# FPGA_Config_GPMC.net
KiCad netlist of a schematic drawn in Altium Designer
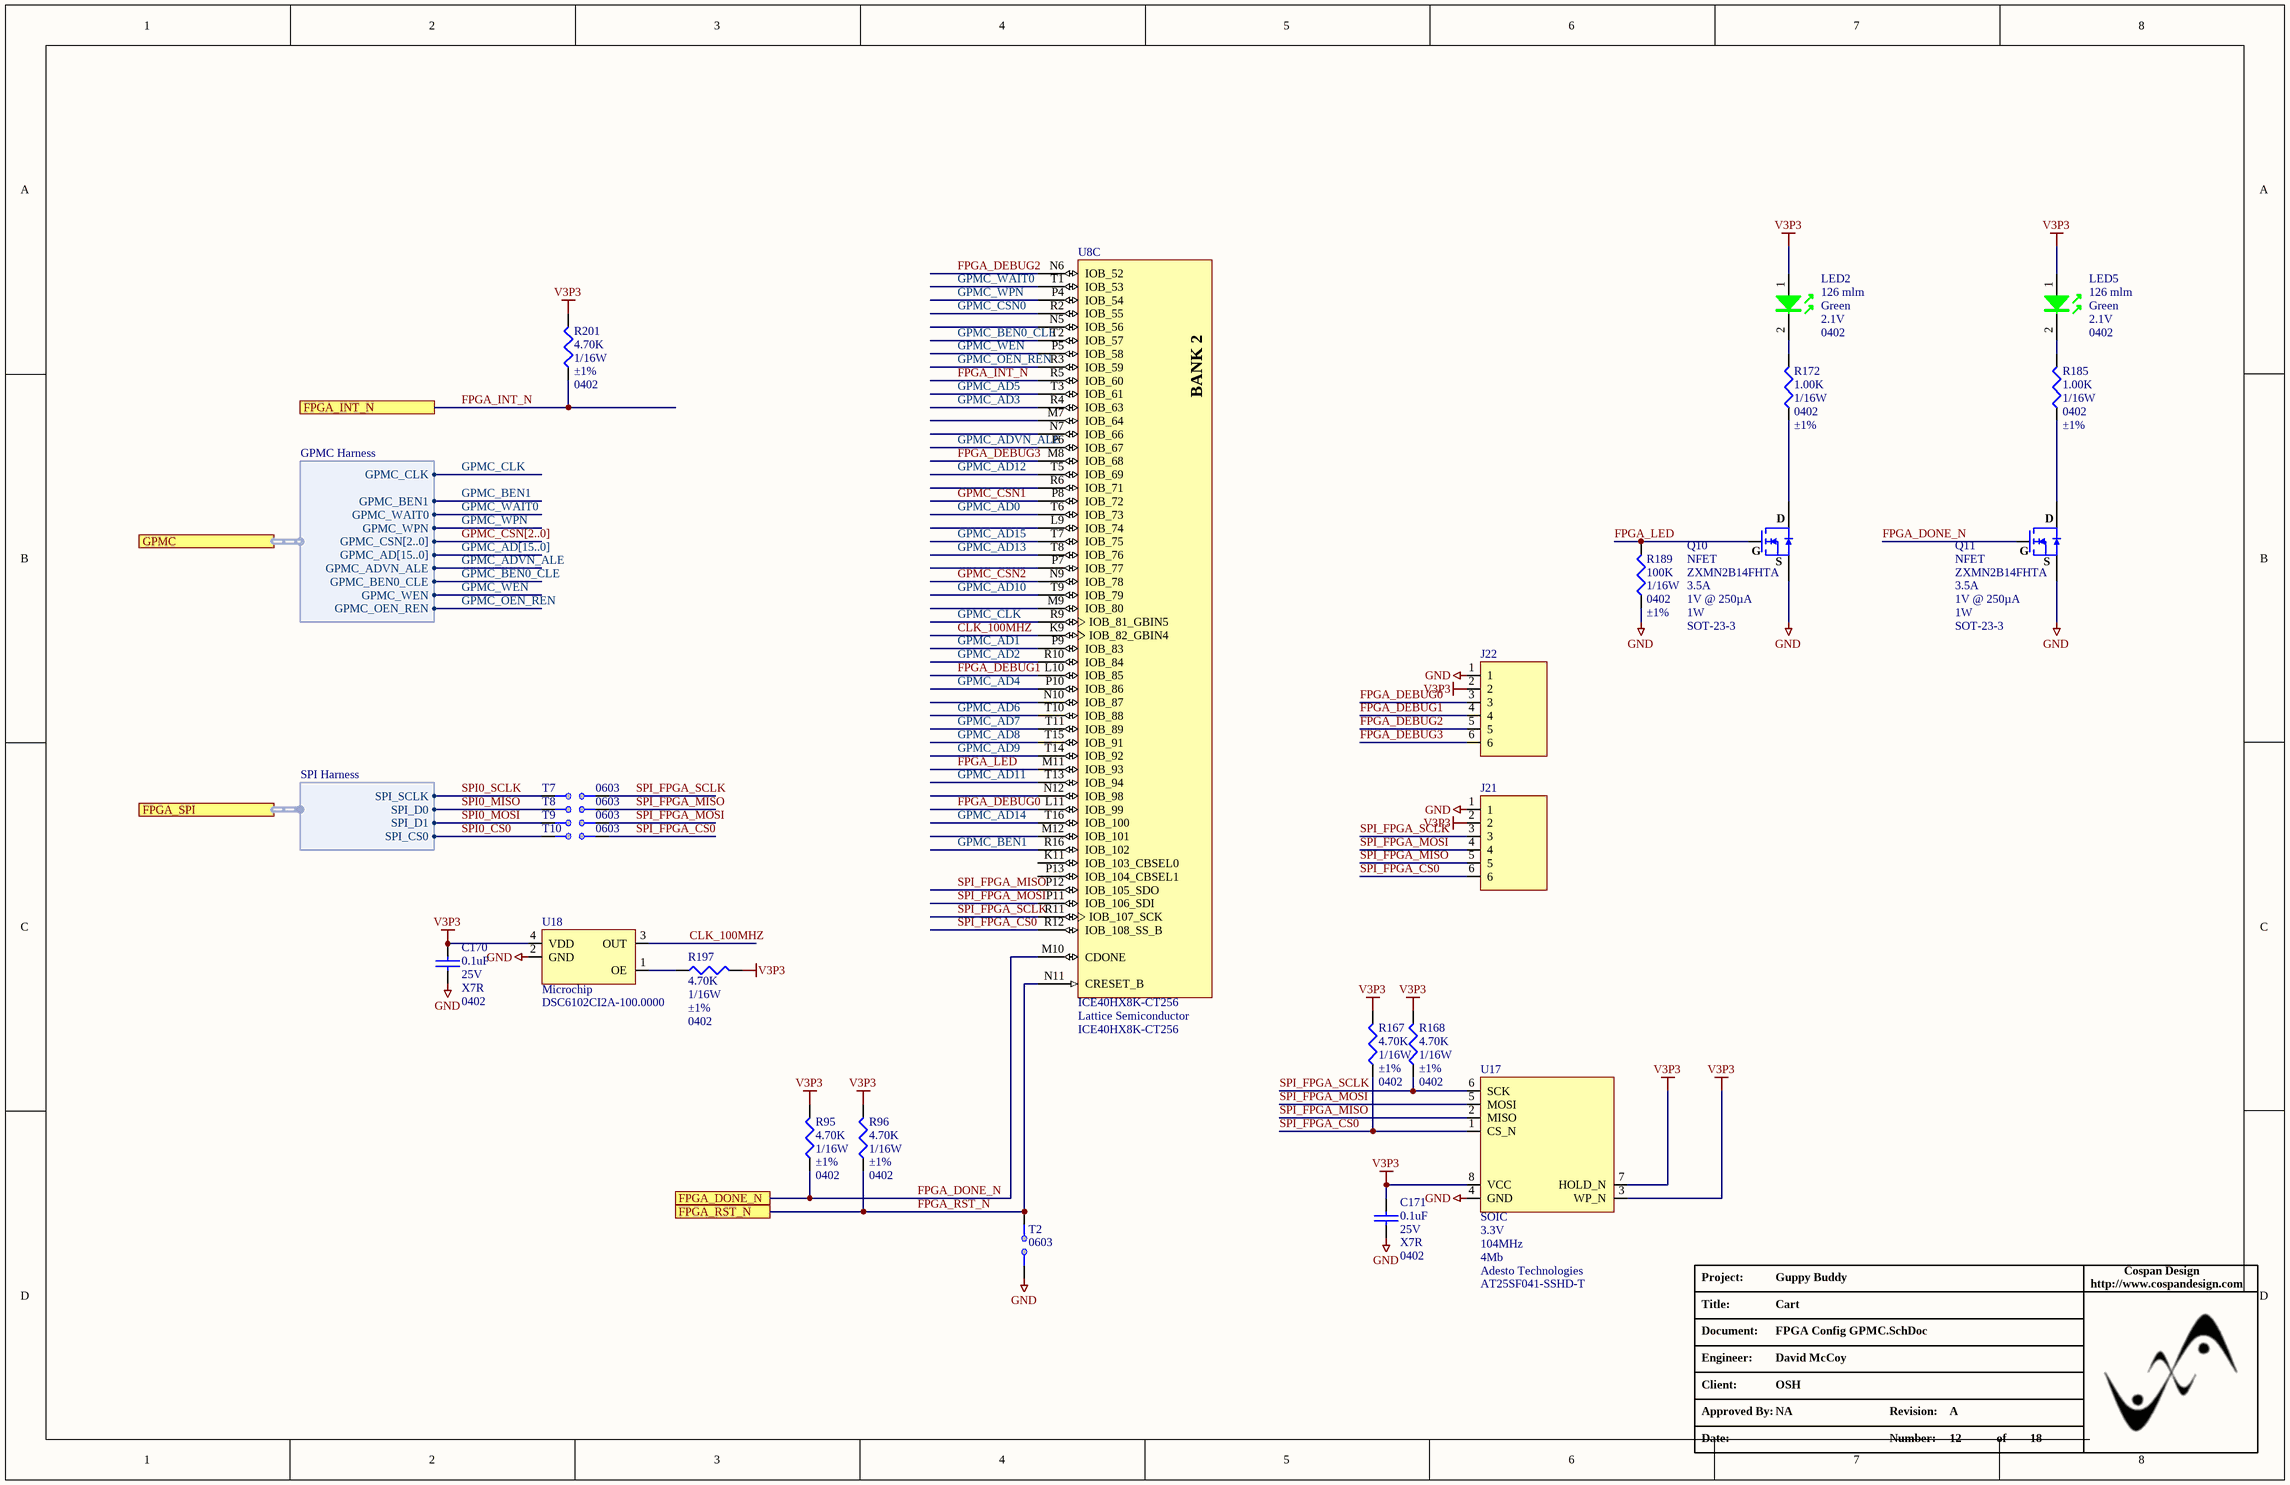
[diagram p0: FPGA Config GPMC.SchDoc]

(export (version "E")
  (design (tool "Eeschema 10.0.6"))
  (components
    (comp (ref "C170")
      (value "C_0402_0.1UF_25V")
      (footprint "C_0402")
      (description "CAP CER 0.1UF 25V X6S 0402")
      (fields
        (field (name "TOLERANCE") "10%")
        (field (name "CAPACITANCE") "0.1uF")
        (field (name "VOLTAGE - RATED") "25V")
        (field (name "TEMPERATURE COEFFICIENT") "X7R")
        (field (name "PACKAGE / CASE") "0402")
      )
      (libsource (lib "Cospan Design") (part "C_0402_0.1UF_25V"))
    )
    (comp (ref "C171")
      (value "C_0402_0.1UF_25V")
      (footprint "C_0402")
      (description "CAP CER 0.1UF 25V X6S 0402")
      (fields
        (field (name "TOLERANCE") "10%")
        (field (name "CAPACITANCE") "0.1uF")
        (field (name "VOLTAGE - RATED") "25V")
        (field (name "TEMPERATURE COEFFICIENT") "X7R")
        (field (name "PACKAGE / CASE") "0402")
      )
      (libsource (lib "Cospan Design") (part "C_0402_0.1UF_25V"))
    )
    (comp (ref "J21")
      (value "J_HDR_1X6_HOLES")
      (footprint "HDR_1X6 _HOLES")
      (description "6 Holes")
      (libsource (lib "Cospan Design") (part "J_HDR_1X6_HOLES"))
    )
    (comp (ref "J22")
      (value "J_HDR_1X6_HOLES")
      (footprint "HDR_1X6 _HOLES")
      (description "6 Holes")
      (libsource (lib "Cospan Design") (part "J_HDR_1X6_HOLES"))
    )
    (comp (ref "LED2")
      (value "LED_GRN_0402")
      (footprint "DIOM1005X07L_GREEN")
      (description "LED 1X0.5MM 570NM GN WTR CLR SMD")
      (fields
        (field (name "MANUFACTURER") "Kingbright Corp")
        (field (name "MANUFACTURER PART NUMBER") "APHHS1005CGCK")
        (field (name "LUMINOUS FLUX @ CURRENT - TEST") "126 mlm")
        (field (name "COLOR") "Green")
        (field (name "VOLTAGE - FORWARD (VF) TYP") "2.1V")
        (field (name "PACKAGE / CASE") "0402")
      )
      (libsource (lib "Main Library") (part "LED_GRN_0402"))
    )
    (comp (ref "LED5")
      (value "LED_GRN_0402")
      (footprint "DIOM1005X07L_GREEN")
      (description "LED 1X0.5MM 570NM GN WTR CLR SMD")
      (fields
        (field (name "MANUFACTURER") "Kingbright Corp")
        (field (name "MANUFACTURER PART NUMBER") "APHHS1005CGCK")
        (field (name "LUMINOUS FLUX @ CURRENT - TEST") "126 mlm")
        (field (name "COLOR") "Green")
        (field (name "VOLTAGE - FORWARD (VF) TYP") "2.1V")
        (field (name "PACKAGE / CASE") "0402")
      )
      (libsource (lib "Main Library") (part "LED_GRN_0402"))
    )
    (comp (ref "Q10")
      (value "NFET")
      (footprint "SOT-23A")
      (description "MOSFET N-CH 20V 3.5A SOT23-3")
      (fields
        (field (name "MANUFACTURER") "Diodes Incorporated")
        (field (name "MANUFACTURER PART NUMBER") "ZXMN2B14FHTA")
        (field (name "CURRENT - CONTINUOUS DRAIN (ID) @ 25° C") "3.5A")
        (field (name "VGS(TH) (MAX) @ ID") "1V @ 250µA")
        (field (name "POWER - MAX") "1W")
        (field (name "PACKAGE / CASE") "SOT-23-3")
      )
      (libsource (lib "Main LibraryX") (part "Q_NFET_3.50A_SOT23"))
    )
    (comp (ref "Q11")
      (value "NFET")
      (footprint "SOT-23A")
      (description "MOSFET N-CH 20V 3.5A SOT23-3")
      (fields
        (field (name "MANUFACTURER") "Diodes Incorporated")
        (field (name "MANUFACTURER PART NUMBER") "ZXMN2B14FHTA")
        (field (name "CURRENT - CONTINUOUS DRAIN (ID) @ 25° C") "3.5A")
        (field (name "VGS(TH) (MAX) @ ID") "1V @ 250µA")
        (field (name "POWER - MAX") "1W")
        (field (name "PACKAGE / CASE") "SOT-23-3")
      )
      (libsource (lib "Main LibraryX") (part "Q_NFET_3.50A_SOT23"))
    )
    (comp (ref "R95")
      (value "4.7k Ohms")
      (footprint "R_0402")
      (description "RES 4.70K OHM 1/16W 1% 0402 SMD")
      (fields
        (field (name "MANUFACTURER") "Yageo")
        (field (name "MANUFACTURER PART NUMBER") "RC0402FR-074K7L")
        (field (name "RESISTANCE IN OHMS") "4.70K")
        (field (name "POWER (WATTS)") "1/16W")
        (field (name "TOLERANCE") "±1%")
        (field (name "CASE") "0402")
      )
      (libsource (lib "Main Library") (part "R_0402_4.70K"))
    )
    (comp (ref "R96")
      (value "4.7k Ohms")
      (footprint "R_0402")
      (description "RES 4.70K OHM 1/16W 1% 0402 SMD")
      (fields
        (field (name "MANUFACTURER") "Yageo")
        (field (name "MANUFACTURER PART NUMBER") "RC0402FR-074K7L")
        (field (name "RESISTANCE IN OHMS") "4.70K")
        (field (name "POWER (WATTS)") "1/16W")
        (field (name "TOLERANCE") "±1%")
        (field (name "CASE") "0402")
      )
      (libsource (lib "Main Library") (part "R_0402_4.70K"))
    )
    (comp (ref "R167")
      (value "4.7k Ohms")
      (footprint "R_0402")
      (description "RES 4.70K OHM 1/16W 1% 0402 SMD")
      (fields
        (field (name "MANUFACTURER") "Yageo")
        (field (name "MANUFACTURER PART NUMBER") "RC0402FR-074K7L")
        (field (name "RESISTANCE IN OHMS") "4.70K")
        (field (name "POWER (WATTS)") "1/16W")
        (field (name "TOLERANCE") "±1%")
        (field (name "CASE") "0402")
      )
      (libsource (lib "Main Library") (part "R_0402_4.70K"))
    )
    (comp (ref "R168")
      (value "4.7k Ohms")
      (footprint "R_0402")
      (description "RES 4.70K OHM 1/16W 1% 0402 SMD")
      (fields
        (field (name "MANUFACTURER") "Yageo")
        (field (name "MANUFACTURER PART NUMBER") "RC0402FR-074K7L")
        (field (name "RESISTANCE IN OHMS") "4.70K")
        (field (name "POWER (WATTS)") "1/16W")
        (field (name "TOLERANCE") "±1%")
        (field (name "CASE") "0402")
      )
      (libsource (lib "Main Library") (part "R_0402_4.70K"))
    )
    (comp (ref "R172")
      (value "1.0k Ohms")
      (footprint "R_0402")
      (description "RES 1.00K OHM 1/16W 1% 0402 SMD")
      (fields
        (field (name "MANUFACTURER") "Yageo")
        (field (name "MANUFACTURER PART NUMBER") "RC0402FR-071KL")
        (field (name "RESISTANCE IN OHMS") "1.00K")
        (field (name "POWER (WATTS)") "1/16W")
        (field (name "CASE") "0402")
        (field (name "TOLERANCE") "±1%")
      )
      (libsource (lib "Main Library") (part "R_0402_1.0K"))
    )
    (comp (ref "R185")
      (value "1.0k Ohms")
      (footprint "R_0402")
      (description "RES 1.00K OHM 1/16W 1% 0402 SMD")
      (fields
        (field (name "MANUFACTURER") "Yageo")
        (field (name "MANUFACTURER PART NUMBER") "RC0402FR-071KL")
        (field (name "RESISTANCE IN OHMS") "1.00K")
        (field (name "POWER (WATTS)") "1/16W")
        (field (name "CASE") "0402")
        (field (name "TOLERANCE") "±1%")
      )
      (libsource (lib "Main Library") (part "R_0402_1.0K"))
    )
    (comp (ref "R189")
      (value "R_0402_100.0K")
      (footprint "R_0402")
      (description "RES 100K OHM 1/16W 1% 0402 SMD")
      (fields
        (field (name "MANUFACTURER") "Stackpole Electronics Inc")
        (field (name "MANUFACTURER PART NUMBER") "RMCF0402FT100K")
        (field (name "RESISTANCE IN OHMS") "100K")
        (field (name "POWER (WATTS)") "1/16W")
        (field (name "CASE") "0402")
        (field (name "TOLERANCE") "±1%")
      )
      (libsource (lib "Main Library") (part "R_0402_100.0K"))
    )
    (comp (ref "R197")
      (value "4.7k Ohms")
      (footprint "R_0402")
      (description "RES 4.70K OHM 1/16W 1% 0402 SMD")
      (fields
        (field (name "MANUFACTURER") "Yageo")
        (field (name "MANUFACTURER PART NUMBER") "RC0402FR-074K7L")
        (field (name "RESISTANCE IN OHMS") "4.70K")
        (field (name "POWER (WATTS)") "1/16W")
        (field (name "TOLERANCE") "±1%")
        (field (name "CASE") "0402")
      )
      (libsource (lib "Main Library") (part "R_0402_4.70K"))
    )
    (comp (ref "R201")
      (value "4.7k Ohms")
      (footprint "R_0402")
      (description "RES 4.70K OHM 1/16W 1% 0402 SMD")
      (fields
        (field (name "MANUFACTURER") "Yageo")
        (field (name "MANUFACTURER PART NUMBER") "RC0402FR-074K7L")
        (field (name "RESISTANCE IN OHMS") "4.70K")
        (field (name "POWER (WATTS)") "1/16W")
        (field (name "TOLERANCE") "±1%")
        (field (name "CASE") "0402")
      )
      (libsource (lib "Main Library") (part "R_0402_4.70K"))
    )
    (comp (ref "T2")
      (value "Place Solder Bridge to Enable")
      (footprint "ERA-0603-SOLDER_JUMPER")
      (description "SOLDER_JUMPER PAD")
      (fields (field (name "CASE") "0603"))
      (libsource (lib "Main Library") (part "T_0603_JUMPER_PAD"))
    )
    (comp (ref "T7")
      (value "Place Solder Bridge to Enable")
      (footprint "ERA-0603-SOLDER_JUMPER")
      (description "SOLDER_JUMPER PAD")
      (fields (field (name "CASE") "0603"))
      (libsource (lib "Main Library") (part "T_0603_JUMPER_PAD"))
    )
    (comp (ref "T8")
      (value "Place Solder Bridge to Enable")
      (footprint "ERA-0603-SOLDER_JUMPER")
      (description "SOLDER_JUMPER PAD")
      (fields (field (name "CASE") "0603"))
      (libsource (lib "Main Library") (part "T_0603_JUMPER_PAD"))
    )
    (comp (ref "T9")
      (value "Place Solder Bridge to Enable")
      (footprint "ERA-0603-SOLDER_JUMPER")
      (description "SOLDER_JUMPER PAD")
      (fields (field (name "CASE") "0603"))
      (libsource (lib "Main Library") (part "T_0603_JUMPER_PAD"))
    )
    (comp (ref "T10")
      (value "Place Solder Bridge to Enable")
      (footprint "ERA-0603-SOLDER_JUMPER")
      (description "SOLDER_JUMPER PAD")
      (fields (field (name "CASE") "0603"))
      (libsource (lib "Main Library") (part "T_0603_JUMPER_PAD"))
    )
    (comp (ref "U8")
      (value "ICE40HX8K-CT256")
      (footprint "LATC-caBGA-256")
      (fields
        (field (name "MANUFACTURER") "Lattice Semiconductor")
        (field (name "MANUFACTURER 1") "Lattice Semiconductor")
        (field (name "MANUFACTURER PART NUMBER 1") "ICE40HX8K-CT256")
      )
      (libsource (lib "Cospan Design") (part "U_ICE40HX8K-CT256"))
    )
    (comp (ref "U17")
      (value "U_AT25SF041-SSHD-T")
      (footprint "SOIC-8")
      (description "Flash Mem Serial-SPI 3.3V 4Mbit 4M x 1bit 8-Pin SOIC T/R")
      (fields
        (field (name "CASE/PACKAGE") "SOIC")
        (field (name "OPERATING SUPPLY VOLTAGE") "3.3V")
        (field (name "MAX FREQUENCY") "104MHz")
        (field (name "DENSITY") "4Mb")
        (field (name "MANUFACTURER 1") "Adesto Technologies")
        (field (name "MANUFACTURER PART NUMBER 1") "AT25SF041-SSHD-T")
      )
      (libsource (lib "Cospan Design") (part "U_AT25SF041-SSHD-T"))
    )
    (comp (ref "U18")
      (value "U_DSC6102CI2A-100.0000")
      (footprint "4-SMD OSC")
      (description "OSC MEMS 100.0000MHZ CMOS SMD")
      (fields
        (field (name "MANUFACTURER 1") "Microchip")
        (field (name "MANUFACTURER PART NUMBER 1") "DSC6102CI2A-100.0000")
      )
      (libsource (lib "Cospan Design") (part "U_DSC6102CI2A-100.0000"))
    )
  )
  (nets
    (net (code "6") (name "/CLK_100MHZ") (class "Default")
      (node (ref "U18") (pin "3") (pinfunction "OUT_3") (pintype "passive"))
      (node (ref "U8") (pin "K9") (pinfunction "IOB_82_GBIN4_K9") (pintype "bidirectional"))
    )
    (net (code "7") (name "/FPGA_DEBUG0") (class "Default")
      (node (ref "J22") (pin "3") (pinfunction "3_3") (pintype "passive"))
      (node (ref "U8") (pin "L11") (pinfunction "IOB_99_L11") (pintype "bidirectional"))
    )
    (net (code "8") (name "/FPGA_DEBUG1") (class "Default")
      (node (ref "J22") (pin "4") (pinfunction "4_4") (pintype "passive"))
      (node (ref "U8") (pin "L10") (pinfunction "IOB_85_L10") (pintype "bidirectional"))
    )
    (net (code "9") (name "/FPGA_DEBUG2") (class "Default")
      (node (ref "J22") (pin "5") (pinfunction "5_5") (pintype "passive"))
      (node (ref "U8") (pin "N6") (pinfunction "IOB_52_N6") (pintype "bidirectional"))
    )
    (net (code "10") (name "/FPGA_DEBUG3") (class "Default")
      (node (ref "J22") (pin "6") (pinfunction "6_6") (pintype "passive"))
      (node (ref "U8") (pin "M8") (pinfunction "IOB_68_M8") (pintype "bidirectional"))
    )
    (net (code "11") (name "/FPGA_DONE_N") (class "Default")
      (node (ref "Q11") (pin "1") (pinfunction "G_1") (pintype "passive"))
      (node (ref "R95") (pin "2") (pinfunction "2_2") (pintype "passive"))
      (node (ref "U8") (pin "M10") (pinfunction "CDONE_M10") (pintype "bidirectional"))
    )
    (net (code "12") (name "/FPGA_INT_N") (class "Default")
      (node (ref "R201") (pin "2") (pinfunction "2_2") (pintype "passive"))
      (node (ref "U8") (pin "R5") (pinfunction "IOB_60_R5") (pintype "bidirectional"))
    )
    (net (code "13") (name "/FPGA_LED") (class "Default")
      (node (ref "Q10") (pin "1") (pinfunction "G_1") (pintype "passive"))
      (node (ref "R189") (pin "1") (pinfunction "1_1") (pintype "passive"))
      (node (ref "U8") (pin "M11") (pinfunction "IOB_93_M11") (pintype "bidirectional"))
    )
    (net (code "14") (name "/FPGA_RST_N") (class "Default")
      (node (ref "R96") (pin "2") (pinfunction "2_2") (pintype "passive"))
      (node (ref "T2") (pin "1") (pinfunction "1_1") (pintype "passive"))
      (node (ref "U8") (pin "N11") (pinfunction "CRESET_B_N11") (pintype "input"))
    )
    (net (code "15") (name "/GPMC_AD0") (class "Default")
      (node (ref "U8") (pin "T6") (pinfunction "IOB_73_T6") (pintype "bidirectional"))
    )
    (net (code "16") (name "/GPMC_AD1") (class "Default")
      (node (ref "U8") (pin "P9") (pinfunction "IOB_83_P9") (pintype "bidirectional"))
    )
    (net (code "17") (name "/GPMC_AD2") (class "Default")
      (node (ref "U8") (pin "R10") (pinfunction "IOB_84_R10") (pintype "bidirectional"))
    )
    (net (code "18") (name "/GPMC_AD3") (class "Default")
      (node (ref "U8") (pin "R4") (pinfunction "IOB_63_R4") (pintype "bidirectional"))
    )
    (net (code "19") (name "/GPMC_AD4") (class "Default")
      (node (ref "U8") (pin "P10") (pinfunction "IOB_86_P10") (pintype "bidirectional"))
    )
    (net (code "20") (name "/GPMC_AD5") (class "Default")
      (node (ref "U8") (pin "T3") (pinfunction "IOB_61_T3") (pintype "bidirectional"))
    )
    (net (code "21") (name "/GPMC_AD6") (class "Default")
      (node (ref "U8") (pin "T10") (pinfunction "IOB_88_T10") (pintype "bidirectional"))
    )
    (net (code "22") (name "/GPMC_AD7") (class "Default")
      (node (ref "U8") (pin "T11") (pinfunction "IOB_89_T11") (pintype "bidirectional"))
    )
    (net (code "23") (name "/GPMC_AD8") (class "Default")
      (node (ref "U8") (pin "T15") (pinfunction "IOB_91_T15") (pintype "bidirectional"))
    )
    (net (code "24") (name "/GPMC_AD9") (class "Default")
      (node (ref "U8") (pin "T14") (pinfunction "IOB_92_T14") (pintype "bidirectional"))
    )
    (net (code "25") (name "/GPMC_AD10") (class "Default")
      (node (ref "U8") (pin "T9") (pinfunction "IOB_79_T9") (pintype "bidirectional"))
    )
    (net (code "26") (name "/GPMC_AD11") (class "Default")
      (node (ref "U8") (pin "T13") (pinfunction "IOB_94_T13") (pintype "bidirectional"))
    )
    (net (code "27") (name "/GPMC_AD12") (class "Default")
      (node (ref "U8") (pin "T5") (pinfunction "IOB_69_T5") (pintype "bidirectional"))
    )
    (net (code "28") (name "/GPMC_AD13") (class "Default")
      (node (ref "U8") (pin "T8") (pinfunction "IOB_76_T8") (pintype "bidirectional"))
    )
    (net (code "29") (name "/GPMC_AD14") (class "Default")
      (node (ref "U8") (pin "T16") (pinfunction "IOB_100_T16") (pintype "bidirectional"))
    )
    (net (code "30") (name "/GPMC_AD15") (class "Default")
      (node (ref "U8") (pin "T7") (pinfunction "IOB_75_T7") (pintype "bidirectional"))
    )
    (net (code "31") (name "/GPMC_ADVN_ALE") (class "Default")
      (node (ref "U8") (pin "P6") (pinfunction "IOB_67_P6") (pintype "bidirectional"))
    )
    (net (code "32") (name "/GPMC_BEN0_CLE") (class "Default")
      (node (ref "U8") (pin "T2") (pinfunction "IOB_57_T2") (pintype "bidirectional"))
    )
    (net (code "33") (name "/GPMC_BEN1") (class "Default")
      (node (ref "U8") (pin "R16") (pinfunction "IOB_102_R16") (pintype "bidirectional"))
    )
    (net (code "34") (name "/GPMC_CLK") (class "Default")
      (node (ref "U8") (pin "R9") (pinfunction "IOB_81_GBIN5_R9") (pintype "bidirectional"))
    )
    (net (code "35") (name "/GPMC_CSN0") (class "Default")
      (node (ref "U8") (pin "R2") (pinfunction "IOB_55_R2") (pintype "bidirectional"))
    )
    (net (code "36") (name "/GPMC_CSN1") (class "Default")
      (node (ref "U8") (pin "P8") (pinfunction "IOB_72_P8") (pintype "bidirectional"))
    )
    (net (code "37") (name "/GPMC_CSN2") (class "Default")
      (node (ref "U8") (pin "N9") (pinfunction "IOB_78_N9") (pintype "bidirectional"))
    )
    (net (code "39") (name "/GPMC_OEN_REN") (class "Default")
      (node (ref "U8") (pin "R3") (pinfunction "IOB_59_R3") (pintype "bidirectional"))
    )
    (net (code "40") (name "/GPMC_WAIT0") (class "Default")
      (node (ref "U8") (pin "T1") (pinfunction "IOB_53_T1") (pintype "bidirectional"))
    )
    (net (code "41") (name "/GPMC_WEN") (class "Default")
      (node (ref "U8") (pin "P5") (pinfunction "IOB_58_P5") (pintype "bidirectional"))
    )
    (net (code "42") (name "/GPMC_WPN") (class "Default")
      (node (ref "U8") (pin "P4") (pinfunction "IOB_54_P4") (pintype "bidirectional"))
    )
    (net (code "44") (name "/SPI0_CS0") (class "Default")
      (node (ref "T10") (pin "1") (pinfunction "1_1") (pintype "passive"))
    )
    (net (code "45") (name "/SPI0_MISO") (class "Default")
      (node (ref "T8") (pin "1") (pinfunction "1_1") (pintype "passive"))
    )
    (net (code "46") (name "/SPI0_MOSI") (class "Default")
      (node (ref "T9") (pin "1") (pinfunction "1_1") (pintype "passive"))
    )
    (net (code "47") (name "/SPI0_SCLK") (class "Default")
      (node (ref "T7") (pin "1") (pinfunction "1_1") (pintype "passive"))
    )
    (net (code "48") (name "/SPI_FPGA_CS0") (class "Default")
      (node (ref "J21") (pin "6") (pinfunction "6_6") (pintype "passive"))
      (node (ref "R167") (pin "2") (pinfunction "2_2") (pintype "passive"))
      (node (ref "T10") (pin "2") (pinfunction "2_2") (pintype "passive"))
      (node (ref "U17") (pin "1") (pinfunction "CS_N_1") (pintype "passive"))
      (node (ref "U8") (pin "R12") (pinfunction "IOB_108_SS_B_R12") (pintype "bidirectional"))
    )
    (net (code "49") (name "/SPI_FPGA_MISO") (class "Default")
      (node (ref "J21") (pin "5") (pinfunction "5_5") (pintype "passive"))
      (node (ref "T8") (pin "2") (pinfunction "2_2") (pintype "passive"))
      (node (ref "U17") (pin "2") (pinfunction "MISO_2") (pintype "passive"))
      (node (ref "U8") (pin "P12") (pinfunction "IOB_105_SDO_P12") (pintype "bidirectional"))
    )
    (net (code "50") (name "/SPI_FPGA_MOSI") (class "Default")
      (node (ref "J21") (pin "4") (pinfunction "4_4") (pintype "passive"))
      (node (ref "T9") (pin "2") (pinfunction "2_2") (pintype "passive"))
      (node (ref "U17") (pin "5") (pinfunction "MOSI_5") (pintype "passive"))
      (node (ref "U8") (pin "P11") (pinfunction "IOB_106_SDI_P11") (pintype "bidirectional"))
    )
    (net (code "51") (name "/SPI_FPGA_SCLK") (class "Default")
      (node (ref "J21") (pin "3") (pinfunction "3_3") (pintype "passive"))
      (node (ref "R168") (pin "2") (pinfunction "2_2") (pintype "passive"))
      (node (ref "T7") (pin "2") (pinfunction "2_2") (pintype "passive"))
      (node (ref "U17") (pin "6") (pinfunction "SCK_6") (pintype "passive"))
      (node (ref "U8") (pin "R11") (pinfunction "IOB_107_SCK_R11") (pintype "bidirectional"))
    )
    (net (code "54") (name "GND") (class "Default")
      (node (ref "C170") (pin "1") (pinfunction "1_1") (pintype "passive"))
      (node (ref "C171") (pin "1") (pinfunction "1_1") (pintype "passive"))
      (node (ref "J21") (pin "1") (pinfunction "1_1") (pintype "passive"))
      (node (ref "J22") (pin "1") (pinfunction "1_1") (pintype "passive"))
      (node (ref "Q10") (pin "2") (pinfunction "S_2") (pintype "passive"))
      (node (ref "Q11") (pin "2") (pinfunction "S_2") (pintype "passive"))
      (node (ref "R189") (pin "2") (pinfunction "2_2") (pintype "passive"))
      (node (ref "T2") (pin "2") (pinfunction "2_2") (pintype "passive"))
      (node (ref "U17") (pin "4") (pinfunction "GND_4") (pintype "passive"))
      (node (ref "U18") (pin "2") (pinfunction "GND_2") (pintype "passive"))
    )
    (net (code "55") (name "Net-(LED2-Pad2)") (class "Default")
      (node (ref "LED2") (pin "2") (pinfunction "2_2") (pintype "passive"))
      (node (ref "R172") (pin "1") (pinfunction "1_1") (pintype "passive"))
    )
    (net (code "56") (name "Net-(LED5-Pad2)") (class "Default")
      (node (ref "LED5") (pin "2") (pinfunction "2_2") (pintype "passive"))
      (node (ref "R185") (pin "1") (pinfunction "1_1") (pintype "passive"))
    )
    (net (code "57") (name "Net-(Q10-D)") (class "Default")
      (node (ref "Q10") (pin "3") (pinfunction "D_3") (pintype "passive"))
      (node (ref "R172") (pin "2") (pinfunction "2_2") (pintype "passive"))
    )
    (net (code "58") (name "Net-(Q11-D)") (class "Default")
      (node (ref "Q11") (pin "3") (pinfunction "D_3") (pintype "passive"))
      (node (ref "R185") (pin "2") (pinfunction "2_2") (pintype "passive"))
    )
    (net (code "59") (name "Net-(U18-OE)") (class "Default")
      (node (ref "R197") (pin "2") (pinfunction "2_2") (pintype "passive"))
      (node (ref "U18") (pin "1") (pinfunction "OE_1") (pintype "passive"))
    )
    (net (code "60") (name "V3P3") (class "Default")
      (node (ref "C170") (pin "2") (pinfunction "2_2") (pintype "passive"))
      (node (ref "C171") (pin "2") (pinfunction "2_2") (pintype "passive"))
      (node (ref "J21") (pin "2") (pinfunction "2_2") (pintype "passive"))
      (node (ref "J22") (pin "2") (pinfunction "2_2") (pintype "passive"))
      (node (ref "LED2") (pin "1") (pinfunction "1_1") (pintype "passive"))
      (node (ref "LED5") (pin "1") (pinfunction "1_1") (pintype "passive"))
      (node (ref "R167") (pin "1") (pinfunction "1_1") (pintype "passive"))
      (node (ref "R168") (pin "1") (pinfunction "1_1") (pintype "passive"))
      (node (ref "R197") (pin "1") (pinfunction "1_1") (pintype "passive"))
      (node (ref "R201") (pin "1") (pinfunction "1_1") (pintype "passive"))
      (node (ref "R95") (pin "1") (pinfunction "1_1") (pintype "passive"))
      (node (ref "R96") (pin "1") (pinfunction "1_1") (pintype "passive"))
      (node (ref "U17") (pin "3") (pinfunction "WP_N_3") (pintype "passive"))
      (node (ref "U17") (pin "7") (pinfunction "HOLD_N_7") (pintype "passive"))
      (node (ref "U17") (pin "8") (pinfunction "VCC_8") (pintype "passive"))
      (node (ref "U18") (pin "4") (pinfunction "VDD_4") (pintype "passive"))
    )
    (net (code "61") (name "unconnected-(U8C-IOB_56-PadN5)") (class "Default")
      (node (ref "U8") (pin "N5") (pinfunction "IOB_56_N5") (pintype "bidirectional"))
    )
    (net (code "62") (name "unconnected-(U8C-IOB_64-PadM7)") (class "Default")
      (node (ref "U8") (pin "M7") (pinfunction "IOB_64_M7") (pintype "bidirectional"))
    )
    (net (code "63") (name "unconnected-(U8C-IOB_66-PadN7)") (class "Default")
      (node (ref "U8") (pin "N7") (pinfunction "IOB_66_N7") (pintype "bidirectional"))
    )
    (net (code "64") (name "unconnected-(U8C-IOB_71-PadR6)") (class "Default")
      (node (ref "U8") (pin "R6") (pinfunction "IOB_71_R6") (pintype "bidirectional"))
    )
    (net (code "65") (name "unconnected-(U8C-IOB_74-PadL9)") (class "Default")
      (node (ref "U8") (pin "L9") (pinfunction "IOB_74_L9") (pintype "bidirectional"))
    )
    (net (code "66") (name "unconnected-(U8C-IOB_77-PadP7)") (class "Default")
      (node (ref "U8") (pin "P7") (pinfunction "IOB_77_P7") (pintype "bidirectional"))
    )
    (net (code "67") (name "unconnected-(U8C-IOB_80-PadM9)") (class "Default")
      (node (ref "U8") (pin "M9") (pinfunction "IOB_80_M9") (pintype "bidirectional"))
    )
    (net (code "68") (name "unconnected-(U8C-IOB_87-PadN10)") (class "Default")
      (node (ref "U8") (pin "N10") (pinfunction "IOB_87_N10") (pintype "bidirectional"))
    )
    (net (code "69") (name "unconnected-(U8C-IOB_98-PadN12)") (class "Default")
      (node (ref "U8") (pin "N12") (pinfunction "IOB_98_N12") (pintype "bidirectional"))
    )
    (net (code "70") (name "unconnected-(U8C-IOB_101-PadM12)") (class "Default")
      (node (ref "U8") (pin "M12") (pinfunction "IOB_101_M12") (pintype "bidirectional"))
    )
    (net (code "71") (name "unconnected-(U8C-IOB_103_CBSEL0-PadK11)") (class "Default")
      (node (ref "U8") (pin "K11") (pinfunction "IOB_103_CBSEL0_K11") (pintype "bidirectional"))
    )
    (net (code "72") (name "unconnected-(U8C-IOB_104_CBSEL1-PadP13)") (class "Default")
      (node (ref "U8") (pin "P13") (pinfunction "IOB_104_CBSEL1_P13") (pintype "bidirectional"))
    )
  )
)
